# Analog_Signals.net
KiCad netlist of a schematic drawn in Altium Designer
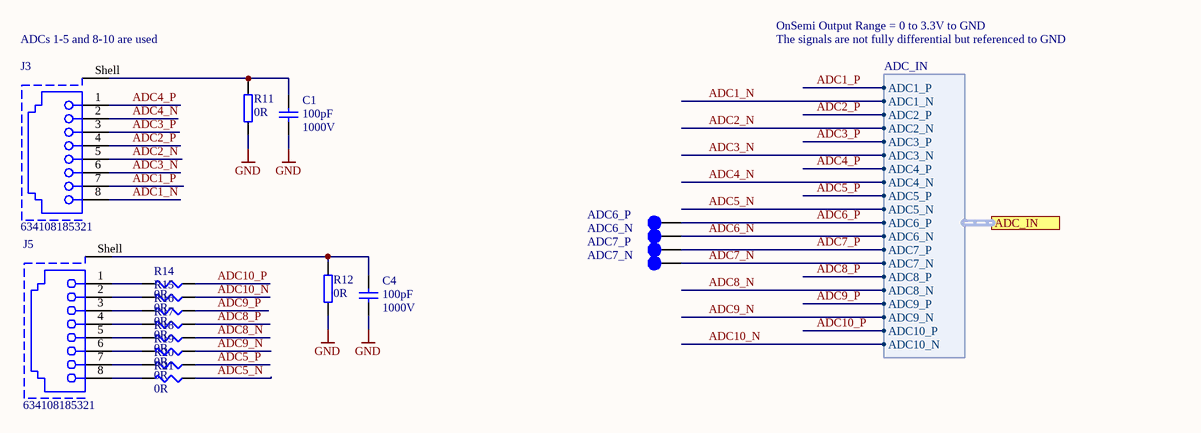
[diagram p0: Analog_Signals.SchDoc]

(export (version "E")
  (design (tool "Eeschema 10.0.6"))
  (components
    (comp (ref "ADC6_N")
      (value "ADC6_N")
      (footprint "TP_1mm")
      (description "Testpoint 1mm")
      (fields (field (name "CREATED") "2018_06_25_AGeiger"))
      (libsource (lib "UltraZOhm_CarrierBoard") (part "TP_1mm"))
    )
    (comp (ref "ADC6_P")
      (value "ADC6_P")
      (footprint "TP_1mm")
      (description "Testpoint 1mm")
      (fields (field (name "CREATED") "2018_06_25_AGeiger"))
      (libsource (lib "UltraZOhm_CarrierBoard") (part "TP_1mm"))
    )
    (comp (ref "ADC7_N")
      (value "ADC7_N")
      (footprint "TP_1mm")
      (description "Testpoint 1mm")
      (fields (field (name "CREATED") "2018_06_25_AGeiger"))
      (libsource (lib "UltraZOhm_CarrierBoard") (part "TP_1mm"))
    )
    (comp (ref "ADC7_P")
      (value "ADC7_P")
      (footprint "TP_1mm")
      (description "Testpoint 1mm")
      (fields (field (name "CREATED") "2018_06_25_AGeiger"))
      (libsource (lib "UltraZOhm_CarrierBoard") (part "TP_1mm"))
    )
    (comp (ref "C1")
      (value "100pF")
      (footprint "C_1206")
      (description "Capacitor 1206")
      (fields
        (field (name "TOLERANCE") "5%")
        (field (name "MF") "Würth Elektronik")
        (field (name "VOLTAGE") "1000V")
        (field (name "CREATED") "2018_06_25_AGeiger")
      )
      (libsource (lib "UltraZohm_ADC") (part "C_1206"))
    )
    (comp (ref "C4")
      (value "100pF")
      (footprint "C_1206")
      (description "Capacitor 1206")
      (fields
        (field (name "TOLERANCE") "5%")
        (field (name "MF") "Würth Elektronik")
        (field (name "VOLTAGE") "1000V")
        (field (name "CREATED") "2018_06_25_AGeiger")
      )
      (libsource (lib "UltraZohm_ADC") (part "C_1206"))
    )
    (comp (ref "J3")
      (value "634108185321")
      (footprint "634108185321")
      (description "WR-MJ Modular Jack SMT Vertical Shielded with Solder Tab 8P8C Top Entry")
      (fields (field (name "MANUFACTURER") "Wurth Elektronik"))
      (libsource (lib "Altium_WR-MJ (rev20b)") (part "634108185321"))
    )
    (comp (ref "J5")
      (value "634108185321")
      (footprint "634108185321")
      (description "WR-MJ Modular Jack SMT Vertical Shielded with Solder Tab 8P8C Top Entry")
      (fields (field (name "MANUFACTURER") "Wurth Elektronik"))
      (libsource (lib "Altium_WR-MJ (rev20b)") (part "634108185321"))
    )
    (comp (ref "R11")
      (value "0R")
      (footprint "RESC1608X06N")
      (fields
        (field (name "MF") "Vishay / Dale")
        (field (name "MPN") "CRCW06031M00FKEAC")
        (field (name "TOLERANCE") "1%")
      )
      (libsource (lib "UltraZohm_ADC") (part "R_0603"))
    )
    (comp (ref "R12")
      (value "0R")
      (footprint "RESC1608X06N")
      (fields
        (field (name "MF") "Vishay / Dale")
        (field (name "MPN") "CRCW06031M00FKEAC")
        (field (name "TOLERANCE") "1%")
      )
      (libsource (lib "UltraZohm_ADC") (part "R_0603"))
    )
    (comp (ref "R14")
      (value "0R")
      (footprint "RESC0603")
      (description "RES SMD")
      (fields (field (name "PART NUMBER") "Generic 1% tol.") (field (name "PUBLISHER") "Generic"))
      (libsource (lib "Res_SMD") (part "RES_SMD"))
    )
    (comp (ref "R15")
      (value "0R")
      (footprint "RESC0603")
      (description "RES SMD")
      (fields (field (name "PART NUMBER") "Generic 1% tol.") (field (name "PUBLISHER") "Generic"))
      (libsource (lib "Res_SMD") (part "RES_SMD"))
    )
    (comp (ref "R16")
      (value "0R")
      (footprint "RESC0603")
      (description "RES SMD")
      (fields (field (name "PART NUMBER") "Generic 1% tol.") (field (name "PUBLISHER") "Generic"))
      (libsource (lib "Res_SMD") (part "RES_SMD"))
    )
    (comp (ref "R17")
      (value "0R")
      (footprint "RESC0603")
      (description "RES SMD")
      (fields (field (name "PART NUMBER") "Generic 1% tol.") (field (name "PUBLISHER") "Generic"))
      (libsource (lib "Res_SMD") (part "RES_SMD"))
    )
    (comp (ref "R18")
      (value "0R")
      (footprint "RESC0603")
      (description "RES SMD")
      (fields (field (name "PART NUMBER") "Generic 1% tol.") (field (name "PUBLISHER") "Generic"))
      (libsource (lib "Res_SMD") (part "RES_SMD"))
    )
    (comp (ref "R19")
      (value "0R")
      (footprint "RESC0603")
      (description "RES SMD")
      (fields (field (name "PART NUMBER") "Generic 1% tol.") (field (name "PUBLISHER") "Generic"))
      (libsource (lib "Res_SMD") (part "RES_SMD"))
    )
    (comp (ref "R20")
      (value "0R")
      (footprint "RESC0603")
      (description "RES SMD")
      (fields (field (name "PART NUMBER") "Generic 1% tol.") (field (name "PUBLISHER") "Generic"))
      (libsource (lib "Res_SMD") (part "RES_SMD"))
    )
    (comp (ref "R21")
      (value "0R")
      (footprint "RESC0603")
      (description "RES SMD")
      (fields (field (name "PART NUMBER") "Generic 1% tol.") (field (name "PUBLISHER") "Generic"))
      (libsource (lib "Res_SMD") (part "RES_SMD"))
    )
  )
  (nets
    (net (code "2") (name "/ADC1_N") (class "Default")
      (node (ref "J3") (pin "8") (pinfunction "8_8") (pintype "passive"))
    )
    (net (code "3") (name "/ADC1_P") (class "Default")
      (node (ref "J3") (pin "7") (pinfunction "7_7") (pintype "passive"))
    )
    (net (code "4") (name "/ADC2_N") (class "Default")
      (node (ref "J3") (pin "5") (pinfunction "5_5") (pintype "passive"))
    )
    (net (code "5") (name "/ADC2_P") (class "Default")
      (node (ref "J3") (pin "4") (pinfunction "4_4") (pintype "passive"))
    )
    (net (code "6") (name "/ADC3_N") (class "Default")
      (node (ref "J3") (pin "6") (pinfunction "6_6") (pintype "passive"))
    )
    (net (code "7") (name "/ADC3_P") (class "Default")
      (node (ref "J3") (pin "3") (pinfunction "3_3") (pintype "passive"))
    )
    (net (code "8") (name "/ADC4_N") (class "Default")
      (node (ref "J3") (pin "2") (pinfunction "2_2") (pintype "passive"))
    )
    (net (code "9") (name "/ADC4_P") (class "Default")
      (node (ref "J3") (pin "1") (pinfunction "1_1") (pintype "passive"))
    )
    (net (code "10") (name "/ADC5_N") (class "Default")
      (node (ref "R21") (pin "1") (pinfunction "1_1") (pintype "passive"))
    )
    (net (code "11") (name "/ADC5_P") (class "Default")
      (node (ref "R20") (pin "1") (pinfunction "1_1") (pintype "passive"))
    )
    (net (code "12") (name "/ADC6_N") (class "Default") (node (ref "ADC6_N") (pin "1") (pintype "passive")))
    (net (code "13") (name "/ADC6_P") (class "Default") (node (ref "ADC6_P") (pin "1") (pintype "passive")))
    (net (code "14") (name "/ADC7_N") (class "Default") (node (ref "ADC7_N") (pin "1") (pintype "passive")))
    (net (code "15") (name "/ADC7_P") (class "Default") (node (ref "ADC7_P") (pin "1") (pintype "passive")))
    (net (code "16") (name "/ADC8_N") (class "Default")
      (node (ref "R18") (pin "1") (pinfunction "1_1") (pintype "passive"))
    )
    (net (code "17") (name "/ADC8_P") (class "Default")
      (node (ref "R17") (pin "1") (pinfunction "1_1") (pintype "passive"))
    )
    (net (code "18") (name "/ADC9_N") (class "Default")
      (node (ref "R19") (pin "1") (pinfunction "1_1") (pintype "passive"))
    )
    (net (code "19") (name "/ADC9_P") (class "Default")
      (node (ref "R16") (pin "1") (pinfunction "1_1") (pintype "passive"))
    )
    (net (code "20") (name "/ADC10_N") (class "Default")
      (node (ref "R15") (pin "1") (pinfunction "1_1") (pintype "passive"))
    )
    (net (code "21") (name "/ADC10_P") (class "Default")
      (node (ref "R14") (pin "1") (pinfunction "1_1") (pintype "passive"))
    )
    (net (code "23") (name "GND") (class "Default")
      (node (ref "C1") (pin "1") (pinfunction "1_1") (pintype "passive"))
      (node (ref "C4") (pin "1") (pinfunction "1_1") (pintype "passive"))
      (node (ref "R11") (pin "1") (pintype "passive"))
      (node (ref "R12") (pin "1") (pintype "passive"))
    )
    (net (code "24") (name "Net-(C1-Pad2)") (class "Default")
      (node (ref "C1") (pin "2") (pinfunction "2_2") (pintype "passive"))
      (node (ref "J3") (pin "Shell") (pinfunction "Shell_Shell") (pintype "passive"))
      (node (ref "R11") (pin "2") (pintype "passive"))
    )
    (net (code "25") (name "Net-(C4-Pad2)") (class "Default")
      (node (ref "C4") (pin "2") (pinfunction "2_2") (pintype "passive"))
      (node (ref "J5") (pin "Shell") (pinfunction "Shell_Shell") (pintype "passive"))
      (node (ref "R12") (pin "2") (pintype "passive"))
    )
    (net (code "26") (name "Net-(J5-Pad1)") (class "Default")
      (node (ref "J5") (pin "1") (pinfunction "1_1") (pintype "passive"))
      (node (ref "R14") (pin "2") (pinfunction "2_2") (pintype "passive"))
    )
    (net (code "27") (name "Net-(J5-Pad2)") (class "Default")
      (node (ref "J5") (pin "2") (pinfunction "2_2") (pintype "passive"))
      (node (ref "R15") (pin "2") (pinfunction "2_2") (pintype "passive"))
    )
    (net (code "28") (name "Net-(J5-Pad3)") (class "Default")
      (node (ref "J5") (pin "3") (pinfunction "3_3") (pintype "passive"))
      (node (ref "R16") (pin "2") (pinfunction "2_2") (pintype "passive"))
    )
    (net (code "29") (name "Net-(J5-Pad4)") (class "Default")
      (node (ref "J5") (pin "4") (pinfunction "4_4") (pintype "passive"))
      (node (ref "R17") (pin "2") (pinfunction "2_2") (pintype "passive"))
    )
    (net (code "30") (name "Net-(J5-Pad5)") (class "Default")
      (node (ref "J5") (pin "5") (pinfunction "5_5") (pintype "passive"))
      (node (ref "R18") (pin "2") (pinfunction "2_2") (pintype "passive"))
    )
    (net (code "31") (name "Net-(J5-Pad6)") (class "Default")
      (node (ref "J5") (pin "6") (pinfunction "6_6") (pintype "passive"))
      (node (ref "R19") (pin "2") (pinfunction "2_2") (pintype "passive"))
    )
    (net (code "32") (name "Net-(J5-Pad7)") (class "Default")
      (node (ref "J5") (pin "7") (pinfunction "7_7") (pintype "passive"))
      (node (ref "R20") (pin "2") (pinfunction "2_2") (pintype "passive"))
    )
    (net (code "33") (name "Net-(J5-Pad8)") (class "Default")
      (node (ref "J5") (pin "8") (pinfunction "8_8") (pintype "passive"))
      (node (ref "R21") (pin "2") (pinfunction "2_2") (pintype "passive"))
    )
  )
)
